# ProDocument_esp32_brewpiless_2024-01-04.net
KiCad netlist of a schematic drawn in EasyEDA Pro
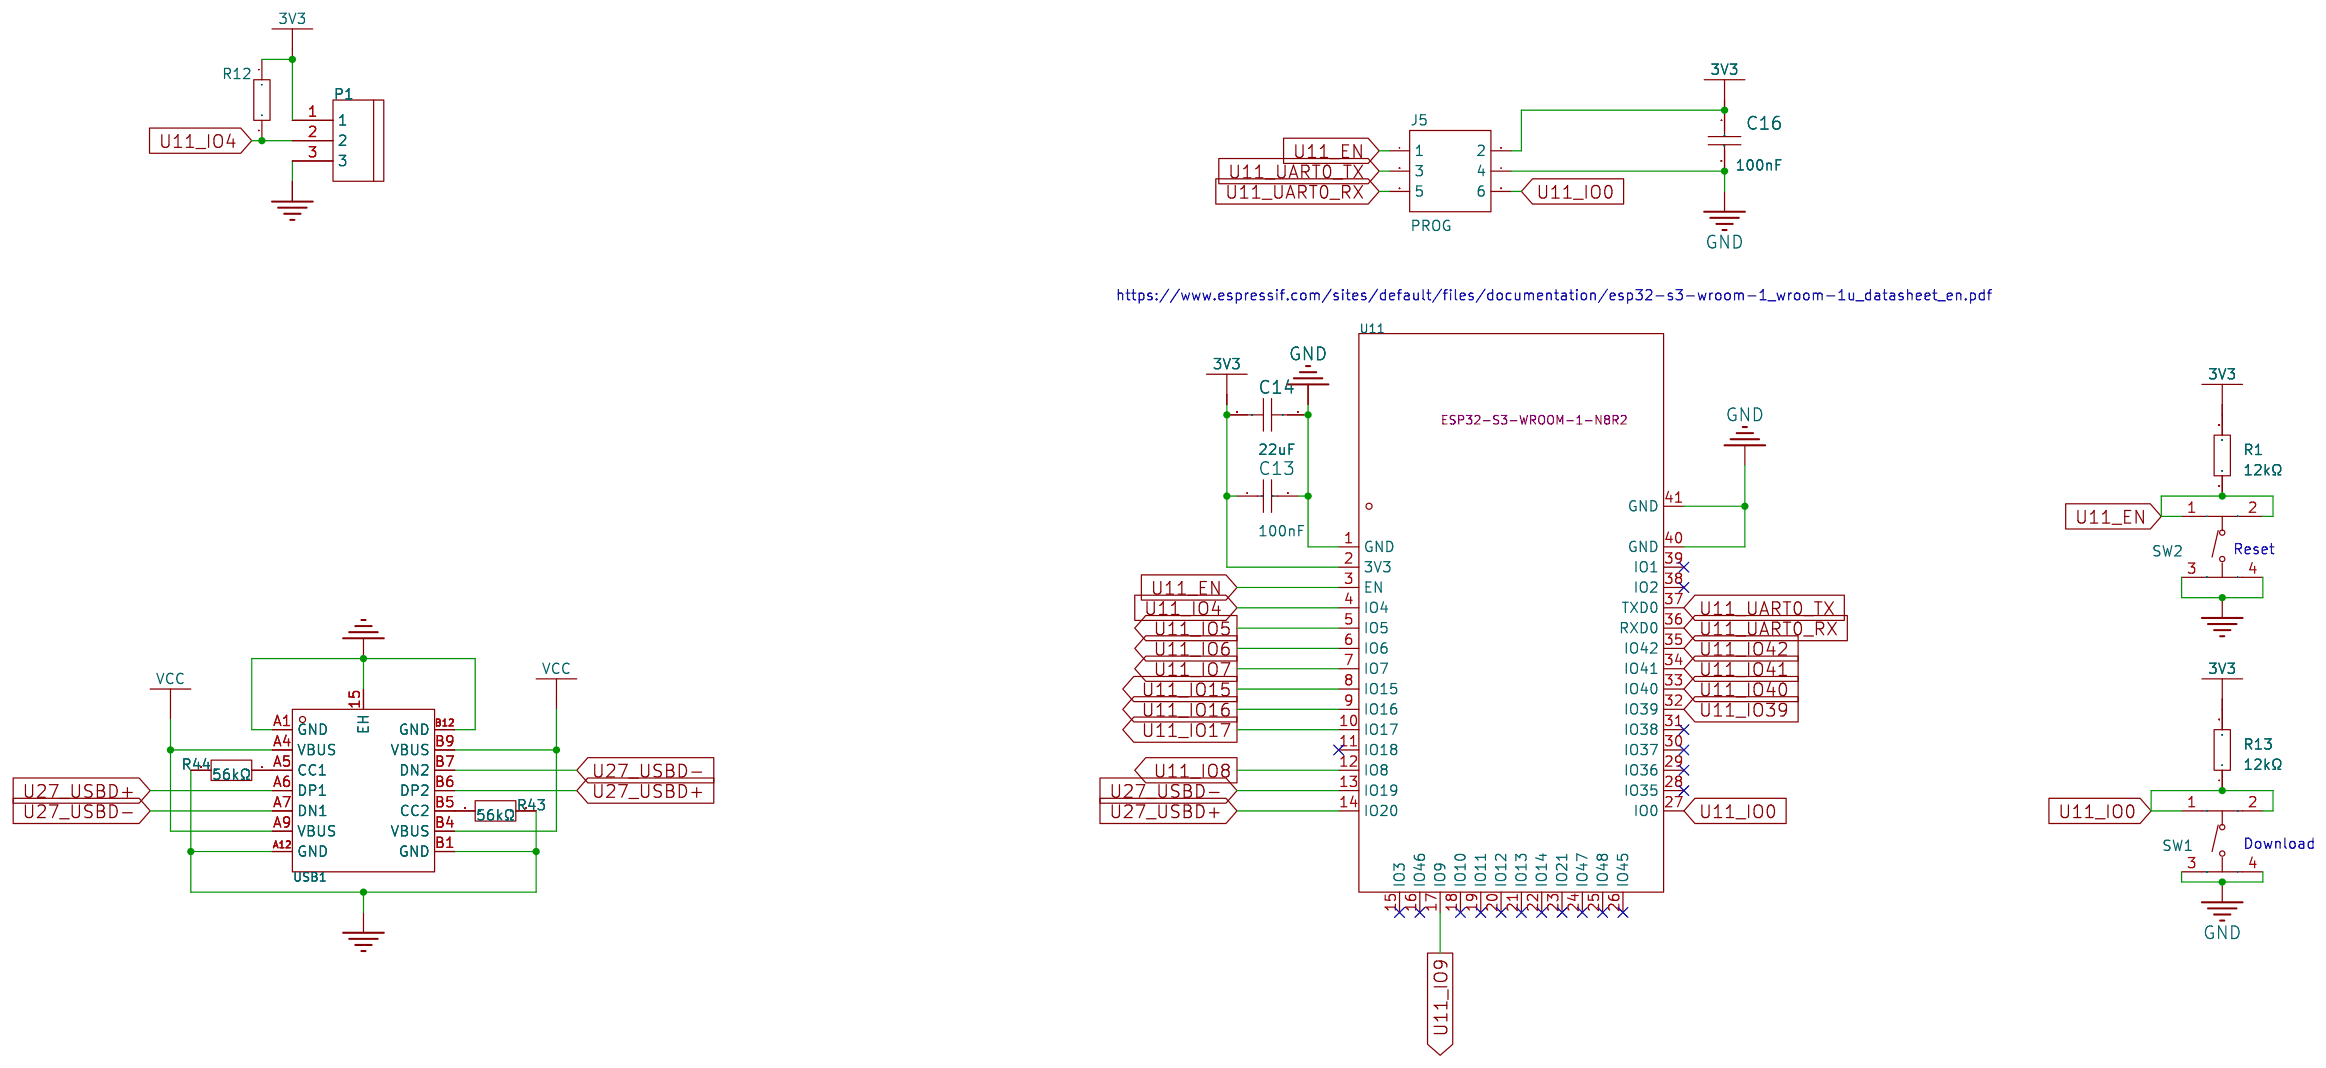
[diagram p0: ESP32]
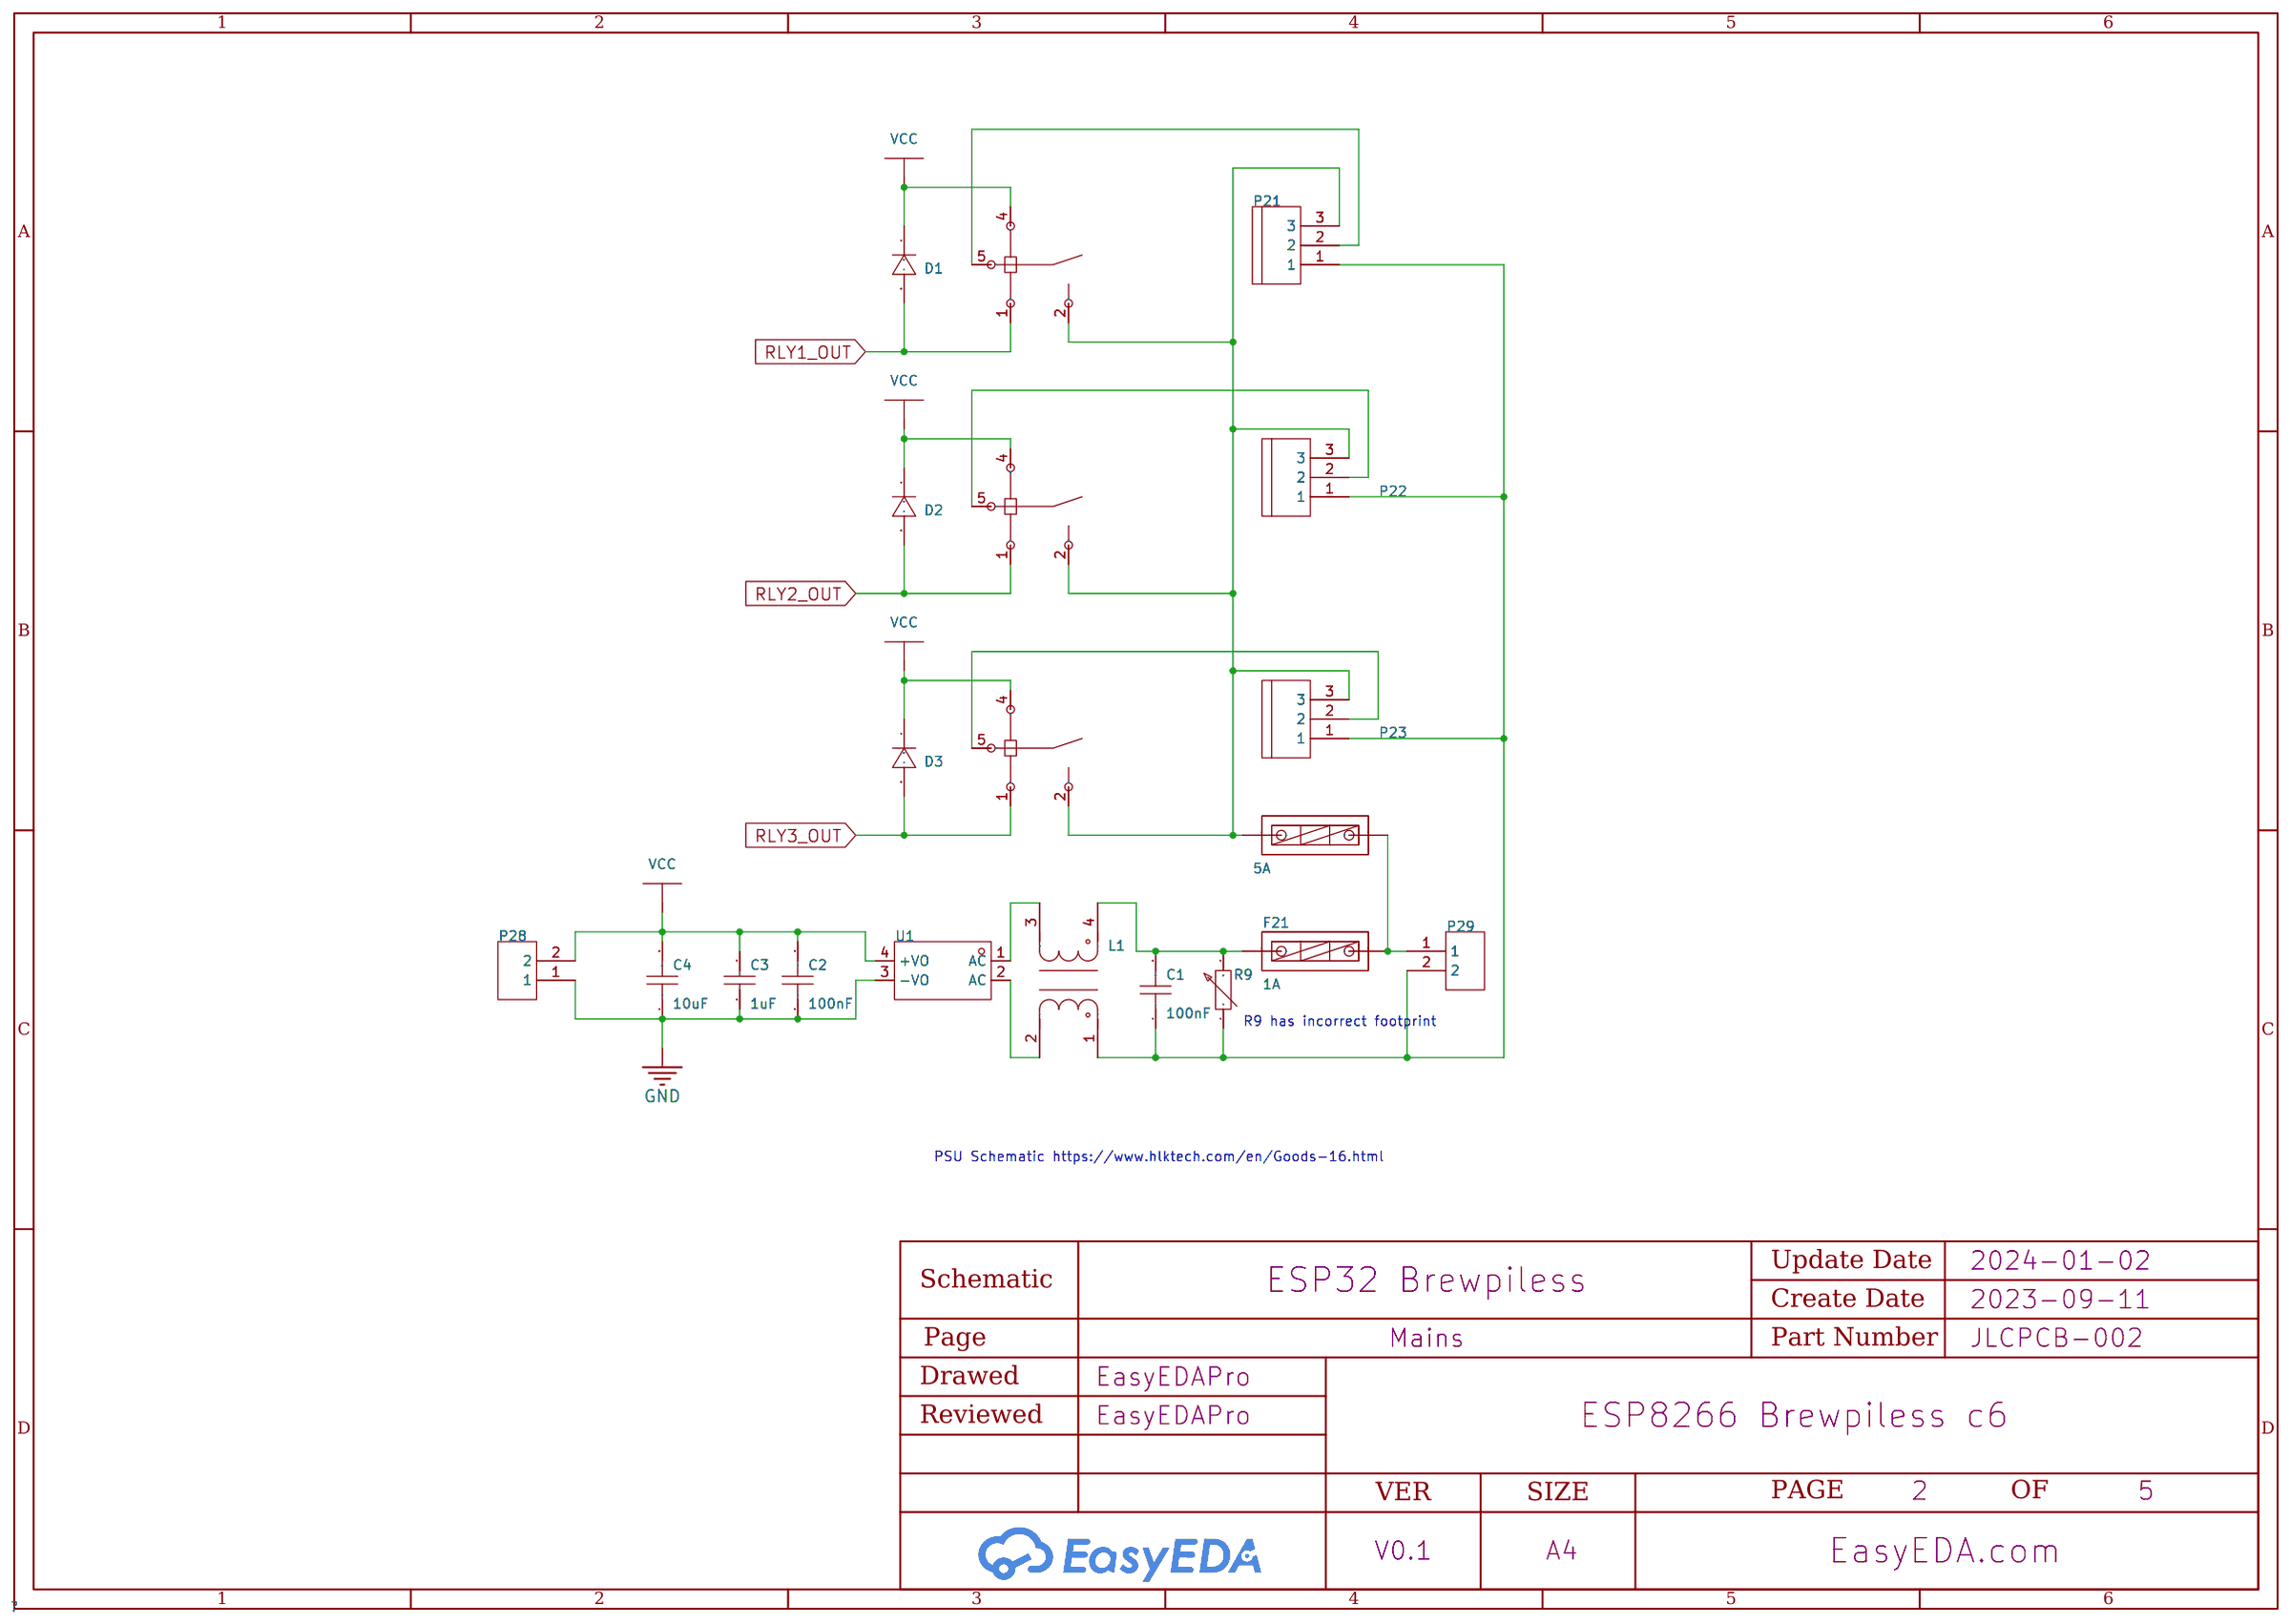
[diagram p1: Mains]
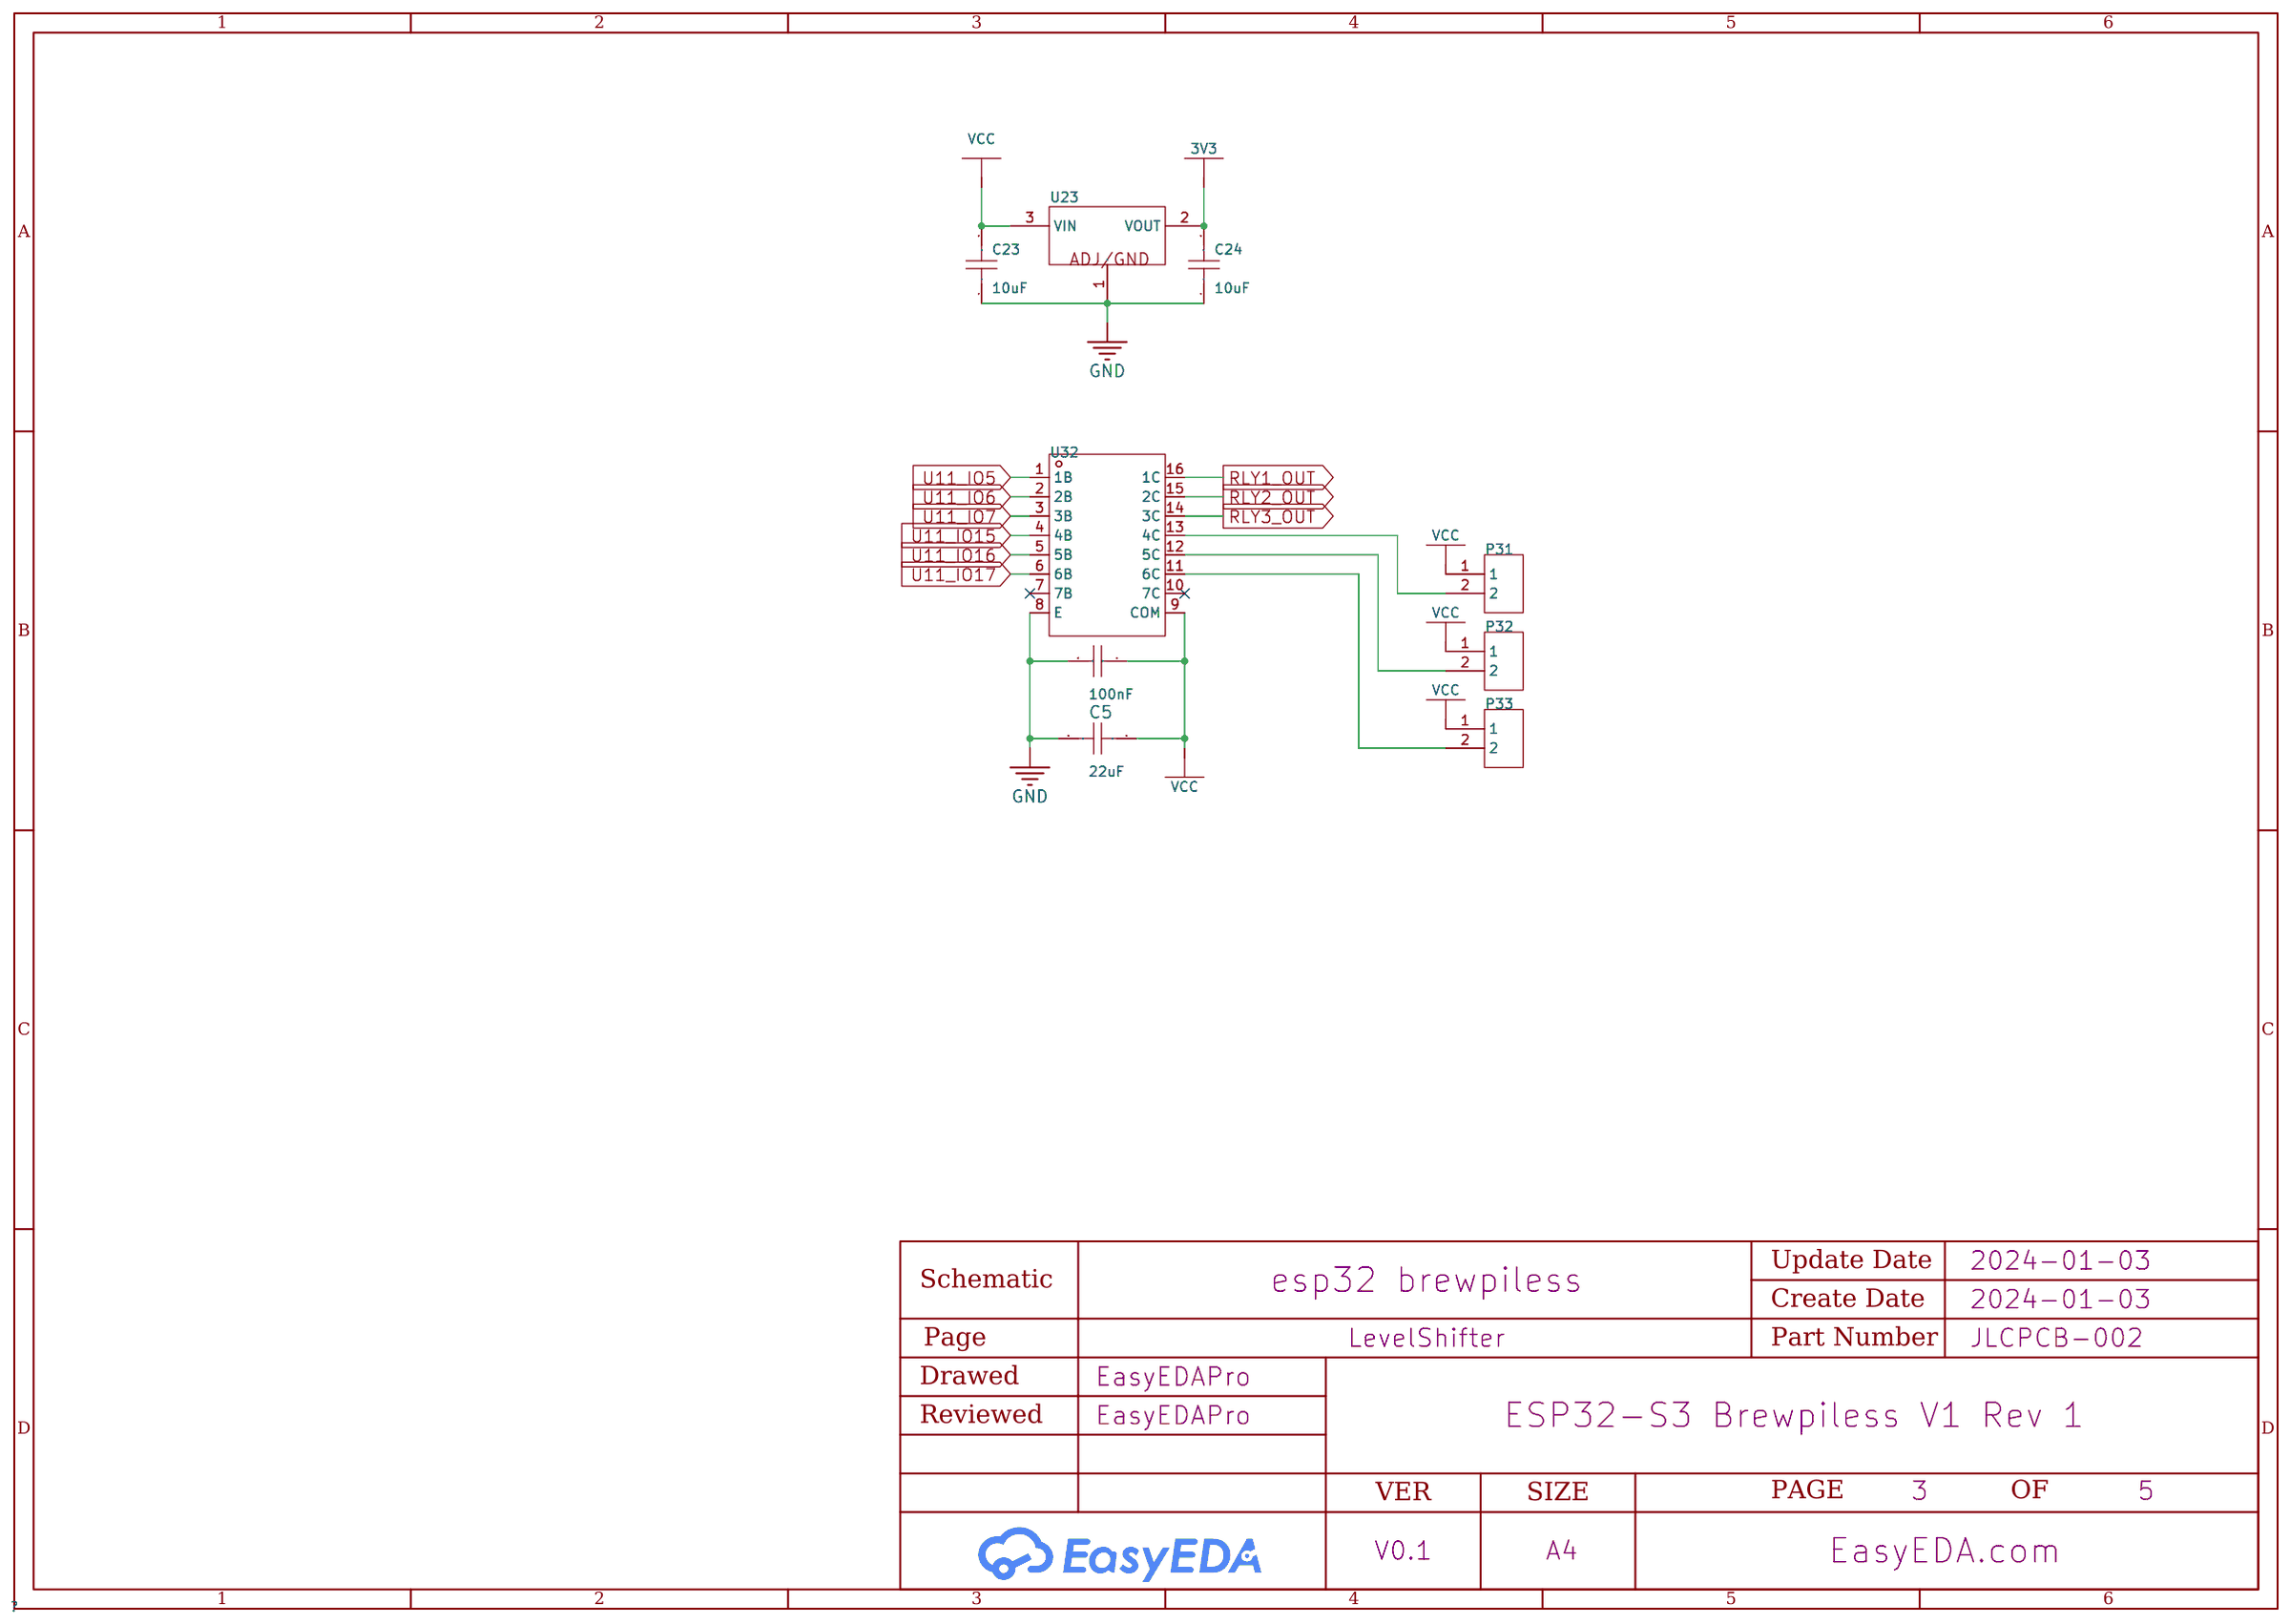
[diagram p2: LevelShifter]
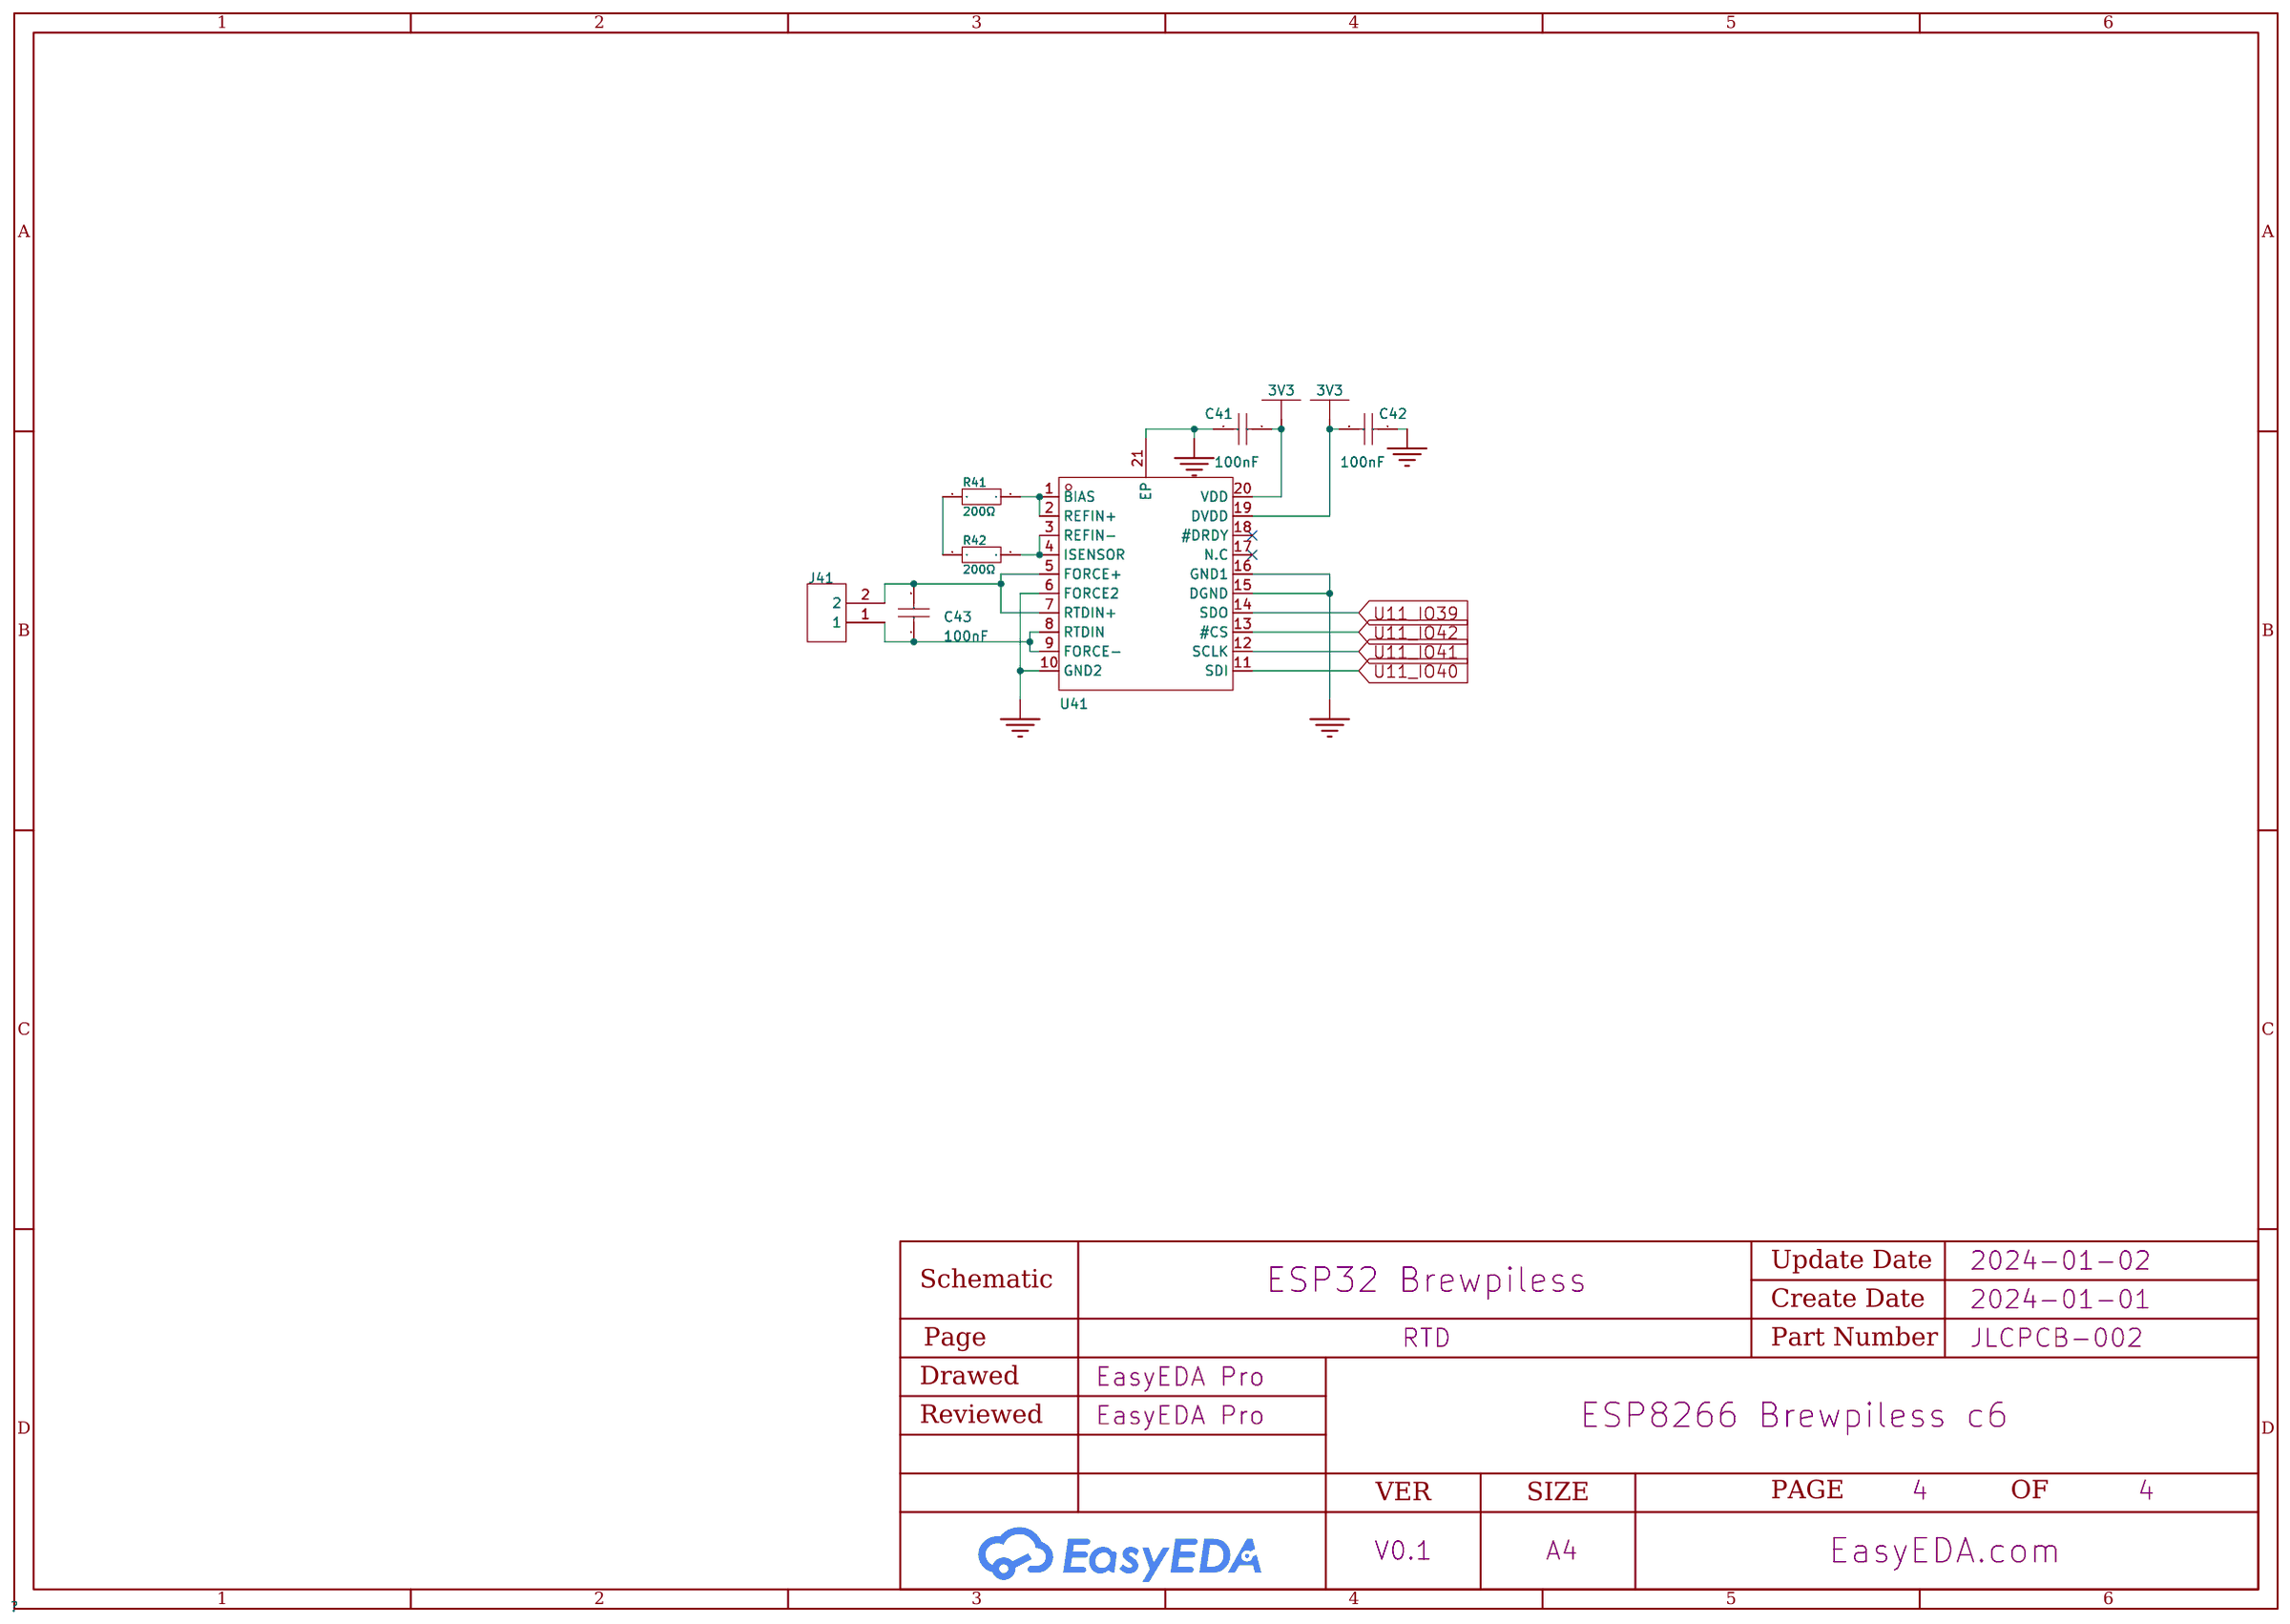
[diagram p3: RTD]
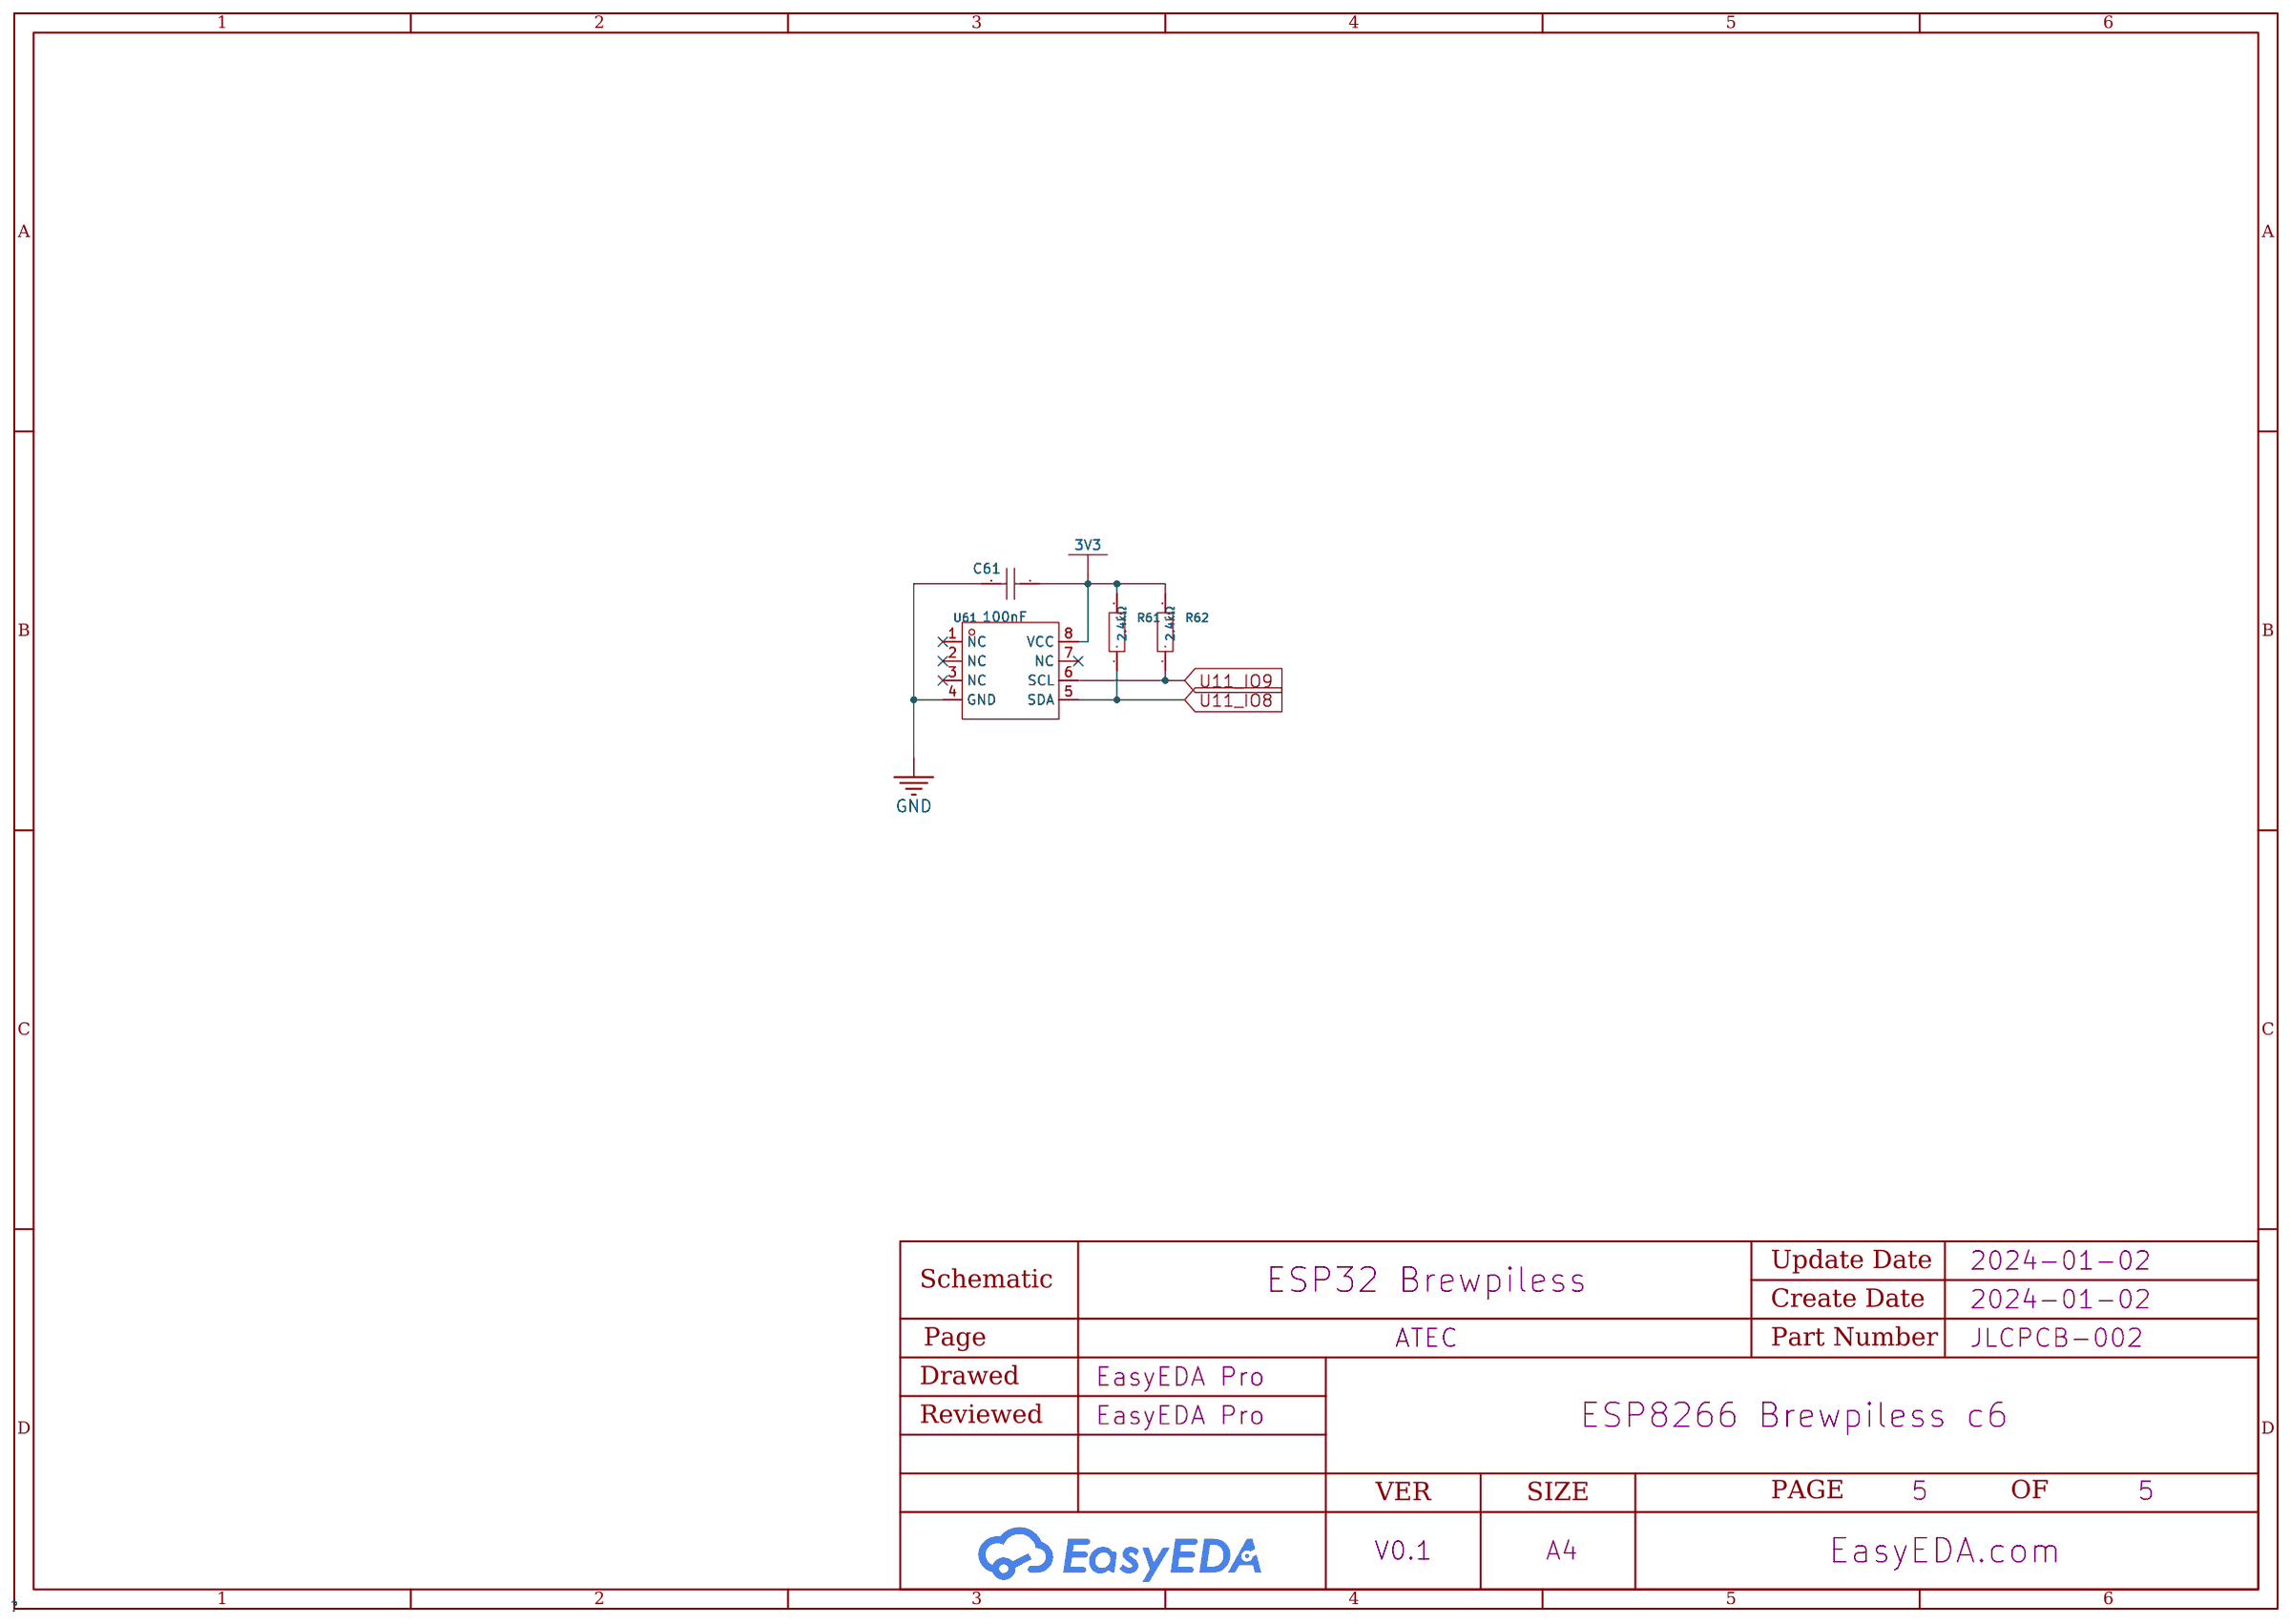
[diagram p4: ATEC]

(export (version "E")
  (design (tool "Eeschema 10.0.6"))
  (components
    (comp (ref "C13")
      (value "100nF")
      (footprint "easyedapro:C0805")
      (fields
        (field (name "Manufacturer Part") "CC0805KRX7R9BB104")
        (field (name "Manufacturer") "YAGEO(国巨)")
      )
      (libsource (lib "easyedapro") (part "CC0805KRX7R9BB104"))
    )
    (comp (ref "C14")
      (value "22uF")
      (footprint "easyedapro:C0805")
      (fields
        (field (name "Manufacturer Part") "CL21A226MAQNNNE")
        (field (name "Manufacturer") "SAMSUNG(三星)")
      )
      (libsource (lib "easyedapro") (part "CL21A226MAQNNNE"))
    )
    (comp (ref "C16")
      (value "100nF")
      (footprint "easyedapro:C0805")
      (fields
        (field (name "Manufacturer Part") "CC0805KRX7R9BB104")
        (field (name "Manufacturer") "YAGEO(国巨)")
      )
      (libsource (lib "easyedapro") (part "CC0805KRX7R9BB104"))
    )
    (comp (ref "J5")
      (value "PROG")
      (footprint "easyedapro:IDC-TH_6P-P2.54_C11214")
      (fields (field (name "Manufacturer Part") "2.54-2*3P简牛") (field (name "Manufacturer") "BOOMELE(博穆精密)"))
      (libsource (lib "easyedapro") (part "HDR-IDC-2.54-2X3P"))
    )
    (comp (ref "P1")
      (value "WJ500V-5.08-3P")
      (footprint "easyedapro:CONN-TH_3P-P5.00_WJ500V-5.08-3P")
      (fields (field (name "Manufacturer") "KANGNEX(康奈克斯电气)"))
      (libsource (lib "easyedapro") (part "WJ500V-5.08-3P-14-00A"))
    )
    (comp (ref "R1")
      (value "12kΩ")
      (footprint "easyedapro:R0805")
      (fields
        (field (name "Manufacturer Part") "0805W8F1202T5E")
        (field (name "Manufacturer") "UNI-ROYAL(厚声)")
      )
      (libsource (lib "easyedapro") (part "0805W8F1202T5E"))
    )
    (comp (ref "R12")
      (value "4.7kΩ")
      (footprint "easyedapro:R0805")
      (fields
        (field (name "Manufacturer Part") "0805W8F4701T5E")
        (field (name "Manufacturer") "UNI-ROYAL(厚声)")
      )
      (libsource (lib "easyedapro") (part "0805W8F4701T5E"))
    )
    (comp (ref "R13")
      (value "12kΩ")
      (footprint "easyedapro:R0805")
      (fields
        (field (name "Manufacturer Part") "0805W8F1202T5E")
        (field (name "Manufacturer") "UNI-ROYAL(厚声)")
      )
      (libsource (lib "easyedapro") (part "0805W8F1202T5E"))
    )
    (comp (ref "R43")
      (value "56kΩ")
      (footprint "easyedapro:R0805")
      (fields (field (name "Manufacturer Part") "ARG05DTC5602") (field (name "Manufacturer") "Viking(光颉)"))
      (libsource (lib "easyedapro") (part "ARG05DTC5602"))
    )
    (comp (ref "R44")
      (value "56kΩ")
      (footprint "easyedapro:R0805")
      (fields (field (name "Manufacturer Part") "ARG05DTC5602") (field (name "Manufacturer") "Viking(光颉)"))
      (libsource (lib "easyedapro") (part "ARG05DTC5602"))
    )
    (comp (ref "SW1")
      (value "TS-1187A-B-A-B")
      (footprint "easyedapro:SW-SMD_4P-L5.1-W5.1-P3.70-LS6.5-TL-2")
      (fields (field (name "Manufacturer") "XKB Connectivity(中国星坤)"))
      (libsource (lib "easyedapro") (part "TS-1187A-B-A-B"))
    )
    (comp (ref "SW2")
      (value "TS-1187A-B-A-B")
      (footprint "easyedapro:SW-SMD_4P-L5.1-W5.1-P3.70-LS6.5-TL-2")
      (fields (field (name "Manufacturer") "XKB Connectivity(中国星坤)"))
      (libsource (lib "easyedapro") (part "TS-1187A-B-A-B"))
    )
    (comp (ref "U11")
      (value "2.4GHz")
      (footprint "easyedapro:WIRELM-SMD_ESP32-S3-WROOM-1")
      (description "Core Processor:ESP32-S3芯片 Support Interface:I2C；GPIO；SPI；PWM；ADC；UART；USB；I2S Frequency:2.4GHz")
      (fields
        (field (name "Manufacturer Part") "ESP32-S3-WROOM-1-N8R2")
        (field (name "Manufacturer") "ESPRESSIF(乐鑫)")
      )
      (libsource (lib "easyedapro") (part "ESP32-S3-WROOM-1(N8R2)"))
    )
    (comp (ref "USB1")
      (value "TYPE-C 14P LTH10.0")
      (footprint "easyedapro:TYPE-C-SMD_918-468K2029Y50001")
      (fields (field (name "Manufacturer") "SHOU HAN(首韩)"))
      (libsource (lib "easyedapro") (part "TYPE-C 14P LTH10.0"))
    )
    (comp (ref "C1")
      (value "100nF")
      (footprint "easyedapro:CAP-TH_L12.0-W5.5-P10.00-D0.6")
      (fields
        (field (name "Manufacturer Part") "MPP104J2W10AJ22620")
        (field (name "Manufacturer") "KNSCHA(科尼盛)")
      )
      (libsource (lib "easyedapro") (part "MPP104J2W10AJ22620"))
    )
    (comp (ref "C2")
      (value "100nF")
      (footprint "easyedapro:CAP-TH_L12.0-W5.5-P10.00-D0.6")
      (fields
        (field (name "Manufacturer Part") "MPP104J2W10AJ22620")
        (field (name "Manufacturer") "KNSCHA(科尼盛)")
      )
      (libsource (lib "easyedapro") (part "MPP104J2W10AJ22620"))
    )
    (comp (ref "C3")
      (value "1uF")
      (footprint "easyedapro:C0805")
      (fields
        (field (name "Manufacturer Part") "CL21B105KBFNNNE")
        (field (name "Manufacturer") "SAMSUNG(三星)")
      )
      (libsource (lib "easyedapro") (part "CL21B105KBFNNNE"))
    )
    (comp (ref "C4")
      (value "10uF")
      (footprint "easyedapro:C0805")
      (fields
        (field (name "Manufacturer Part") "GRM21BR61H106KE43L")
        (field (name "Manufacturer") "muRata(村田)")
      )
      (libsource (lib "easyedapro") (part "GRM21BR61H106KE43L"))
    )
    (comp (ref "D1")
      (value "SM4007PL")
      (footprint "easyedapro:SOD-123F_L2.8-W1.8-LS3.7-RD")
      (fields (field (name "Manufacturer") "MDD"))
      (libsource (lib "easyedapro") (part "SM4007PL"))
    )
    (comp (ref "D2")
      (value "SM4007PL")
      (footprint "easyedapro:SOD-123F_L2.8-W1.8-LS3.7-RD")
      (fields (field (name "Manufacturer") "MDD"))
      (libsource (lib "easyedapro") (part "SM4007PL"))
    )
    (comp (ref "D3")
      (value "SM4007PL")
      (footprint "easyedapro:SOD-123F_L2.8-W1.8-LS3.7-RD")
      (fields (field (name "Manufacturer") "MDD"))
      (libsource (lib "easyedapro") (part "SM4007PL"))
    )
    (comp (ref "F21")
      (value "~")
      (footprint "easyedapro:FUSE-TH_5X20RHOSFUSECLIP-SEAT")
      (fields (field (name "Manufacturer Part") "5x20环保保险管夹/座") (field (name "Manufacturer") "xcfuse(旭程)"))
      (libsource (lib "easyedapro") (part "5x20 RHOS Fuse clip/seat"))
    )
    (comp (ref "F22")
      (value "5A")
      (footprint "easyedapro:FUSE-TH_5X20RHOSFUSECLIP-SEAT")
      (fields (field (name "Manufacturer Part") "5x20环保保险管夹/座") (field (name "Manufacturer") "xcfuse(旭程)"))
      (libsource (lib "easyedapro") (part "5x20 RHOS Fuse clip/seat"))
    )
    (comp (ref "F210")
      (value "1A")
      (footprint "easyedapro:FUSE-TH_5X20RHOSFUSECLIP-SEAT")
      (fields (field (name "Manufacturer Part") "5x20环保保险管夹/座") (field (name "Manufacturer") "xcfuse(旭程)"))
      (libsource (lib "easyedapro") (part "5x20 RHOS Fuse clip/seat"))
    )
    (comp (ref "F220")
      (value "10A")
      (footprint "easyedapro:FUSE-TH_5X20RHOSFUSECLIP-SEAT")
      (fields (field (name "Manufacturer Part") "5x20环保保险管夹/座") (field (name "Manufacturer") "xcfuse(旭程)"))
      (libsource (lib "easyedapro") (part "5x20 RHOS Fuse clip/seat"))
    )
    (comp (ref "K1")
      (value "~")
      (footprint "easyedapro:RELAY-TH_973-XXVDC-SL-A")
      (fields
        (field (name "Manufacturer Part") "973-5VDC-SL-A15A250VAC")
        (field (name "Manufacturer") "NHC(汇龙仓)")
      )
      (libsource (lib "easyedapro") (part "973-5VDC-SL-A 15A250VAC"))
    )
    (comp (ref "K2")
      (value "~")
      (footprint "easyedapro:RELAY-TH_973-XXVDC-SL-A")
      (fields
        (field (name "Manufacturer Part") "973-5VDC-SL-A15A250VAC")
        (field (name "Manufacturer") "NHC(汇龙仓)")
      )
      (libsource (lib "easyedapro") (part "973-5VDC-SL-A 15A250VAC"))
    )
    (comp (ref "K3")
      (value "~")
      (footprint "easyedapro:RELAY-TH_973-XXVDC-SL-A")
      (fields
        (field (name "Manufacturer Part") "973-5VDC-SL-A15A250VAC")
        (field (name "Manufacturer") "NHC(汇龙仓)")
      )
      (libsource (lib "easyedapro") (part "973-5VDC-SL-A 15A250VAC"))
    )
    (comp (ref "L1")
      (value "~")
      (footprint "easyedapro:FILTER-TH_UU10.5Y-10MH")
      (description "Number of Lines:2 Inductance @ Frequency:10mH@1kHz DC Resistance (DCR):750mΩ")
      (fields (field (name "Manufacturer Part") "UU10.5Y-10mH") (field (name "Manufacturer") "FH(风华)"))
      (libsource (lib "easyedapro") (part "UU10.5Y-10mH"))
    )
    (comp (ref "P21")
      (value "WJ500V-5.08-3P")
      (footprint "easyedapro:CONN-TH_3P-P5.00_WJ500V-5.08-3P")
      (fields (field (name "Manufacturer") "KANGNEX(康奈克斯电气)"))
      (libsource (lib "easyedapro") (part "WJ500V-5.08-3P-14-00A"))
    )
    (comp (ref "P22")
      (value "WJ500V-5.08-3P")
      (footprint "easyedapro:CONN-TH_3P-P5.00_WJ500V-5.08-3P")
      (fields (field (name "Manufacturer") "KANGNEX(康奈克斯电气)"))
      (libsource (lib "easyedapro") (part "WJ500V-5.08-3P-14-00A"))
    )
    (comp (ref "P23")
      (value "WJ500V-5.08-3P")
      (footprint "easyedapro:CONN-TH_3P-P5.00_WJ500V-5.08-3P")
      (fields (field (name "Manufacturer") "KANGNEX(康奈克斯电气)"))
      (libsource (lib "easyedapro") (part "WJ500V-5.08-3P-14-00A"))
    )
    (comp (ref "P28")
      (value "WJ500V-5.08-2P")
      (footprint "easyedapro:CONN-TH_2P-P5.00_WJ500V-5.08-2P")
      (fields (field (name "Manufacturer") "KANGNEX(康奈克斯电气)"))
      (libsource (lib "easyedapro") (part "WJ500V-5.08-2P-14-00A"))
    )
    (comp (ref "P29")
      (value "WJ500V-5.08-2P")
      (footprint "easyedapro:CONN-TH_2P-P5.00_WJ500V-5.08-2P")
      (fields (field (name "Manufacturer") "KANGNEX(康奈克斯电气)"))
      (libsource (lib "easyedapro") (part "WJ500V-5.08-2P-14-00A"))
    )
    (comp (ref "R9")
      (value "10D561K")
      (footprint "easyedapro:RES-TH_L13.0-W6.0-P7.50-D0.9-S6.00")
      (fields (field (name "Manufacturer") "HEL(鸿志)"))
      (libsource (lib "easyedapro") (part "10D561K"))
    )
    (comp (ref "U1")
      (value "~")
      (footprint "easyedapro:PWRM-TH_HLK-5M05")
      (fields (field (name "Manufacturer Part") "HLK-5M05") (field (name "Manufacturer") "HI-LINK(海凌科)"))
      (libsource (lib "easyedapro") (part "HLK-5M05"))
    )
    (comp (ref "C5")
      (value "22uF")
      (footprint "easyedapro:C0805")
      (fields
        (field (name "Manufacturer Part") "CL21A226MAQNNNE")
        (field (name "Manufacturer") "SAMSUNG(三星)")
      )
      (libsource (lib "easyedapro") (part "CL21A226MAQNNNE"))
    )
    (comp (ref "C22")
      (value "100nF")
      (footprint "easyedapro:C0805")
      (fields
        (field (name "Manufacturer Part") "CC0805KRX7R9BB104")
        (field (name "Manufacturer") "YAGEO(国巨)")
      )
      (libsource (lib "easyedapro") (part "CC0805KRX7R9BB104"))
    )
    (comp (ref "C23")
      (value "10uF")
      (footprint "easyedapro:C0805")
      (fields
        (field (name "Manufacturer Part") "GRM21BR61H106KE43L")
        (field (name "Manufacturer") "muRata(村田)")
      )
      (libsource (lib "easyedapro") (part "GRM21BR61H106KE43L"))
    )
    (comp (ref "C24")
      (value "10uF")
      (footprint "easyedapro:C0805")
      (fields
        (field (name "Manufacturer Part") "GRM21BR61H106KE43L")
        (field (name "Manufacturer") "muRata(村田)")
      )
      (libsource (lib "easyedapro") (part "GRM21BR61H106KE43L"))
    )
    (comp (ref "P31")
      (value "WJ500V-5.08-2P")
      (footprint "easyedapro:CONN-TH_2P-P5.00_WJ500V-5.08-2P")
      (fields (field (name "Manufacturer") "KANGNEX(康奈克斯电气)"))
      (libsource (lib "easyedapro") (part "WJ500V-5.08-2P-14-00A"))
    )
    (comp (ref "P32")
      (value "WJ500V-5.08-2P")
      (footprint "easyedapro:CONN-TH_2P-P5.00_WJ500V-5.08-2P")
      (fields (field (name "Manufacturer") "KANGNEX(康奈克斯电气)"))
      (libsource (lib "easyedapro") (part "WJ500V-5.08-2P-14-00A"))
    )
    (comp (ref "P33")
      (value "WJ500V-5.08-2P")
      (footprint "easyedapro:CONN-TH_2P-P5.00_WJ500V-5.08-2P")
      (fields (field (name "Manufacturer") "KANGNEX(康奈克斯电气)"))
      (libsource (lib "easyedapro") (part "WJ500V-5.08-2P-14-00A"))
    )
    (comp (ref "U23")
      (value "~")
      (footprint "easyedapro:TO-252-2_L6.6-W6.1-P4.57-LS9.9-TL-CW")
      (fields (field (name "Manufacturer Part") "LM1117RS-3.3") (field (name "Manufacturer") "HTC"))
      (libsource (lib "easyedapro") (part "LM1117RS-3.3"))
    )
    (comp (ref "U32")
      (value "~")
      (footprint "easyedapro:SOIC-16_L9.9-W3.9-P1.27-LS6.0-BL")
      (fields (field (name "Manufacturer Part") "ULN2003ADR") (field (name "Manufacturer") "TI(德州仪器)"))
      (libsource (lib "easyedapro") (part "ULN2003ADR"))
    )
    (comp (ref "C41")
      (value "100nF")
      (footprint "easyedapro:C0805")
      (fields
        (field (name "Manufacturer Part") "CC0805KRX7R9BB104")
        (field (name "Manufacturer") "YAGEO(国巨)")
      )
      (libsource (lib "easyedapro") (part "CC0805KRX7R9BB104"))
    )
    (comp (ref "C42")
      (value "100nF")
      (footprint "easyedapro:C0805")
      (fields
        (field (name "Manufacturer Part") "CC0805KRX7R9BB104")
        (field (name "Manufacturer") "YAGEO(国巨)")
      )
      (libsource (lib "easyedapro") (part "CC0805KRX7R9BB104"))
    )
    (comp (ref "C43")
      (value "100nF")
      (footprint "easyedapro:C0805")
      (fields
        (field (name "Manufacturer Part") "CC0805KRX7R9BB104")
        (field (name "Manufacturer") "YAGEO(国巨)")
      )
      (libsource (lib "easyedapro") (part "CC0805KRX7R9BB104"))
    )
    (comp (ref "J41")
      (value "WJ500V-5.08-2P")
      (footprint "easyedapro:CONN-TH_2P-P5.00_WJ500V-5.08-2P")
      (fields (field (name "Manufacturer") "KANGNEX(康奈克斯电气)"))
      (libsource (lib "easyedapro") (part "WJ500V-5.08-2P-14-00A"))
    )
    (comp (ref "R41")
      (value "200Ω")
      (footprint "easyedapro:R0805")
      (fields
        (field (name "Manufacturer Part") "0805W8F2000T5E")
        (field (name "Manufacturer") "UNI-ROYAL(厚声)")
      )
      (libsource (lib "easyedapro") (part "0805W8F2000T5E"))
    )
    (comp (ref "R42")
      (value "200Ω")
      (footprint "easyedapro:R0805")
      (fields
        (field (name "Manufacturer Part") "0805W8F2000T5E")
        (field (name "Manufacturer") "UNI-ROYAL(厚声)")
      )
      (libsource (lib "easyedapro") (part "0805W8F2000T5E"))
    )
    (comp (ref "U41")
      (value "MAX31865ATP+T")
      (footprint "easyedapro:QFN-20_L5.0-W5.0-P0.65-BL-EP")
      (fields (field (name "Manufacturer") "ADI(亚德诺)"))
      (libsource (lib "easyedapro") (part "MAX31865ATP+T"))
    )
    (comp (ref "C61")
      (value "100nF")
      (footprint "easyedapro:C0805")
      (fields
        (field (name "Manufacturer Part") "CC0805KRX7R9BB104")
        (field (name "Manufacturer") "YAGEO(国巨)")
      )
      (libsource (lib "easyedapro") (part "CC0805KRX7R9BB104"))
    )
    (comp (ref "R61")
      (value "2.4kΩ")
      (footprint "easyedapro:R0805")
      (fields
        (field (name "Manufacturer Part") "0805W8F2401T5E")
        (field (name "Manufacturer") "UNI-ROYAL(厚声)")
      )
      (libsource (lib "easyedapro") (part "0805W8F2401T5E"))
    )
    (comp (ref "R62")
      (value "2.4kΩ")
      (footprint "easyedapro:R0805")
      (fields
        (field (name "Manufacturer Part") "0805W8F2401T5E")
        (field (name "Manufacturer") "UNI-ROYAL(厚声)")
      )
      (libsource (lib "easyedapro") (part "0805W8F2401T5E"))
    )
    (comp (ref "U61")
      (value "ATECC608A-SSHDA-T")
      (footprint "easyedapro:SOIC-8_L4.9-W3.9-P1.27-LS6.0-BL")
      (fields (field (name "Manufacturer") "MICROCHIP(美国微芯)"))
      (libsource (lib "easyedapro") (part "ATECC608A-SSHDA-T_C616024"))
    )
  )
  (nets
    (net (code "1") (name "3V3") (class "Default")
      (node (ref "C13") (pin "1") (pinfunction "1_1") (pintype "input"))
      (node (ref "C14") (pin "2") (pinfunction "2_2") (pintype "input"))
      (node (ref "C16") (pin "1") (pinfunction "1_1") (pintype "input"))
      (node (ref "C24") (pin "2") (pinfunction "2_2") (pintype "input"))
      (node (ref "C41") (pin "2") (pinfunction "2_2") (pintype "input"))
      (node (ref "C42") (pin "2") (pinfunction "2_2") (pintype "input"))
      (node (ref "C61") (pin "2") (pinfunction "2_2") (pintype "input"))
      (node (ref "J5") (pin "2") (pinfunction "2_2") (pintype "input"))
      (node (ref "P1") (pin "1") (pinfunction "1_1") (pintype "input"))
      (node (ref "R1") (pin "2") (pinfunction "2_2") (pintype "input"))
      (node (ref "R12") (pin "1") (pinfunction "1_1") (pintype "input"))
      (node (ref "R13") (pin "2") (pinfunction "2_2") (pintype "input"))
      (node (ref "R61") (pin "2") (pinfunction "2_2") (pintype "input"))
      (node (ref "R62") (pin "2") (pinfunction "2_2") (pintype "input"))
      (node (ref "U11") (pin "2") (pinfunction "3V3_2") (pintype "input"))
      (node (ref "U23") (pin "2") (pinfunction "VOUT_2") (pintype "input"))
      (node (ref "U41") (pin "19") (pinfunction "DVDD_19") (pintype "input"))
      (node (ref "U41") (pin "20") (pinfunction "VDD_20") (pintype "input"))
      (node (ref "U61") (pin "8") (pinfunction "VCC_8") (pintype "input"))
    )
    (net (code "2") (name "GND") (class "Default")
      (node (ref "C13") (pin "2") (pinfunction "2_2") (pintype "input"))
      (node (ref "C14") (pin "1") (pinfunction "1_1") (pintype "input"))
      (node (ref "C16") (pin "2") (pinfunction "2_2") (pintype "input"))
      (node (ref "C2") (pin "1") (pinfunction "1_1") (pintype "input"))
      (node (ref "C22") (pin "2") (pinfunction "2_2") (pintype "input"))
      (node (ref "C23") (pin "1") (pinfunction "1_1") (pintype "input"))
      (node (ref "C24") (pin "1") (pinfunction "1_1") (pintype "input"))
      (node (ref "C3") (pin "1") (pinfunction "1_1") (pintype "input"))
      (node (ref "C4") (pin "1") (pinfunction "1_1") (pintype "input"))
      (node (ref "C41") (pin "1") (pinfunction "1_1") (pintype "input"))
      (node (ref "C42") (pin "1") (pinfunction "1_1") (pintype "input"))
      (node (ref "C5") (pin "2") (pinfunction "2_2") (pintype "input"))
      (node (ref "C61") (pin "1") (pinfunction "1_1") (pintype "input"))
      (node (ref "J5") (pin "4") (pinfunction "4_4") (pintype "input"))
      (node (ref "P1") (pin "3") (pinfunction "3_3") (pintype "input"))
      (node (ref "P28") (pin "1") (pinfunction "1_1") (pintype "input"))
      (node (ref "R43") (pin "1") (pinfunction "1_1") (pintype "input"))
      (node (ref "R44") (pin "2") (pinfunction "2_2") (pintype "input"))
      (node (ref "SW1") (pin "3") (pinfunction "C_3") (pintype "input"))
      (node (ref "SW1") (pin "4") (pinfunction "D_4") (pintype "input"))
      (node (ref "SW2") (pin "3") (pinfunction "C_3") (pintype "input"))
      (node (ref "SW2") (pin "4") (pinfunction "D_4") (pintype "input"))
      (node (ref "U1") (pin "3") (pinfunction "-VO_3") (pintype "input"))
      (node (ref "U11") (pin "1") (pinfunction "GND_1") (pintype "input"))
      (node (ref "U11") (pin "40") (pinfunction "GND_40") (pintype "input"))
      (node (ref "U11") (pin "41") (pinfunction "GND_41") (pintype "input"))
      (node (ref "U23") (pin "1") (pinfunction "ADJ_1") (pintype "input"))
      (node (ref "U32") (pin "8") (pinfunction "E_8") (pintype "input"))
      (node (ref "U41") (pin "10") (pinfunction "GND2_10") (pintype "input"))
      (node (ref "U41") (pin "15") (pinfunction "DGND_15") (pintype "input"))
      (node (ref "U41") (pin "16") (pinfunction "GND1_16") (pintype "input"))
      (node (ref "U41") (pin "21") (pinfunction "EP_21") (pintype "input"))
      (node (ref "U41") (pin "6") (pinfunction "FORCE2_6") (pintype "input"))
      (node (ref "U61") (pin "4") (pinfunction "GND_4") (pintype "input"))
      (node (ref "USB1") (pin "15") (pinfunction "EH_15") (pintype "input"))
      (node (ref "USB1") (pin "A1") (pinfunction "GND_A1") (pintype "input"))
      (node (ref "USB1") (pin "A12") (pinfunction "GND_A12") (pintype "input"))
      (node (ref "USB1") (pin "B1") (pinfunction "GND_B1") (pintype "input"))
      (node (ref "USB1") (pin "B12") (pinfunction "GND_B12") (pintype "input"))
    )
    (net (code "3") (name "Net-(C1-Pad1)") (class "Default")
      (node (ref "C1") (pin "1") (pinfunction "1_1") (pintype "input"))
      (node (ref "L1") (pin "1") (pinfunction "1_1") (pintype "input"))
      (node (ref "P21") (pin "1") (pinfunction "1_1") (pintype "input"))
      (node (ref "P22") (pin "1") (pinfunction "1_1") (pintype "input"))
      (node (ref "P23") (pin "1") (pinfunction "1_1") (pintype "input"))
      (node (ref "P29") (pin "2") (pinfunction "2_2") (pintype "input"))
      (node (ref "R9") (pin "1") (pinfunction "1_1") (pintype "input"))
    )
    (net (code "4") (name "Net-(C1-Pad2)") (class "Default")
      (node (ref "C1") (pin "2") (pinfunction "2_2") (pintype "input"))
      (node (ref "F21") (pin "1") (pinfunction "1_1") (pintype "input"))
      (node (ref "L1") (pin "4") (pinfunction "4_4") (pintype "input"))
      (node (ref "R9") (pin "2") (pinfunction "2_2") (pintype "input"))
    )
    (net (code "5") (name "Net-(F22-Pad1)") (class "Default")
      (node (ref "F22") (pin "1") (pinfunction "1_1") (pintype "input"))
      (node (ref "K1") (pin "2") (pinfunction "2_2") (pintype "input"))
      (node (ref "K2") (pin "2") (pinfunction "2_2") (pintype "input"))
      (node (ref "K3") (pin "2") (pinfunction "2_2") (pintype "input"))
      (node (ref "P21") (pin "3") (pinfunction "3_3") (pintype "input"))
      (node (ref "P22") (pin "3") (pinfunction "3_3") (pintype "input"))
      (node (ref "P23") (pin "3") (pinfunction "3_3") (pintype "input"))
    )
    (net (code "6") (name "Net-(F210-Pad1)") (class "Default")
      (node (ref "F210") (pin "1") (pinfunction "1_1") (pintype "input"))
      (node (ref "F220") (pin "1") (pinfunction "1_1") (pintype "input"))
      (node (ref "P29") (pin "1") (pinfunction "1_1") (pintype "input"))
    )
    (net (code "7") (name "Net-(K1-Pad5)") (class "Default")
      (node (ref "K1") (pin "5") (pinfunction "5_5") (pintype "input"))
      (node (ref "P21") (pin "2") (pinfunction "2_2") (pintype "input"))
    )
    (net (code "8") (name "Net-(K2-Pad5)") (class "Default")
      (node (ref "K2") (pin "5") (pinfunction "5_5") (pintype "input"))
      (node (ref "P22") (pin "2") (pinfunction "2_2") (pintype "input"))
    )
    (net (code "9") (name "Net-(K3-Pad5)") (class "Default")
      (node (ref "K3") (pin "5") (pinfunction "5_5") (pintype "input"))
      (node (ref "P23") (pin "2") (pinfunction "2_2") (pintype "input"))
    )
    (net (code "10") (name "Net-(L1-Pad2)") (class "Default")
      (node (ref "L1") (pin "2") (pinfunction "2_2") (pintype "input"))
      (node (ref "U1") (pin "2") (pinfunction "AC_2") (pintype "input"))
    )
    (net (code "11") (name "Net-(L1-Pad3)") (class "Default")
      (node (ref "L1") (pin "3") (pinfunction "3_3") (pintype "input"))
      (node (ref "U1") (pin "1") (pinfunction "AC_1") (pintype "input"))
    )
    (net (code "12") (name "Net-(R41-Pad2)") (class "Default")
      (node (ref "R41") (pin "2") (pinfunction "2_2") (pintype "input"))
      (node (ref "R42") (pin "2") (pinfunction "2_2") (pintype "input"))
    )
    (net (code "13") (name "Net-(U32-4C)") (class "Default")
      (node (ref "P31") (pin "2") (pinfunction "2_2") (pintype "input"))
      (node (ref "U32") (pin "13") (pinfunction "4C_13") (pintype "input"))
    )
    (net (code "14") (name "Net-(U32-5C)") (class "Default")
      (node (ref "P32") (pin "2") (pinfunction "2_2") (pintype "input"))
      (node (ref "U32") (pin "12") (pinfunction "5C_12") (pintype "input"))
    )
    (net (code "15") (name "Net-(U32-6C)") (class "Default")
      (node (ref "P33") (pin "2") (pinfunction "2_2") (pintype "input"))
      (node (ref "U32") (pin "11") (pinfunction "6C_11") (pintype "input"))
    )
    (net (code "16") (name "Net-(U41-BIAS)") (class "Default")
      (node (ref "R41") (pin "1") (pinfunction "1_1") (pintype "input"))
      (node (ref "U41") (pin "1") (pinfunction "BIAS_1") (pintype "input"))
      (node (ref "U41") (pin "2") (pinfunction "REFIN+_2") (pintype "input"))
    )
    (net (code "17") (name "Net-(U41-FORCE+)") (class "Default")
      (node (ref "C43") (pin "2") (pinfunction "2_2") (pintype "input"))
      (node (ref "J41") (pin "2") (pinfunction "2_2") (pintype "input"))
      (node (ref "U41") (pin "5") (pinfunction "FORCE+_5") (pintype "input"))
      (node (ref "U41") (pin "7") (pinfunction "RTDIN+_7") (pintype "input"))
    )
    (net (code "18") (name "Net-(U41-FORCE-)") (class "Default")
      (node (ref "C43") (pin "1") (pinfunction "1_1") (pintype "input"))
      (node (ref "J41") (pin "1") (pinfunction "1_1") (pintype "input"))
      (node (ref "U41") (pin "8") (pinfunction "RTDIN_8") (pintype "input"))
      (node (ref "U41") (pin "9") (pinfunction "FORCE-_9") (pintype "input"))
    )
    (net (code "19") (name "Net-(U41-ISENSOR)") (class "Default")
      (node (ref "R42") (pin "1") (pinfunction "1_1") (pintype "input"))
      (node (ref "U41") (pin "3") (pinfunction "REFIN-_3") (pintype "input"))
      (node (ref "U41") (pin "4") (pinfunction "ISENSOR_4") (pintype "input"))
    )
    (net (code "20") (name "Net-(USB1-CC1)") (class "Default")
      (node (ref "R44") (pin "1") (pinfunction "1_1") (pintype "input"))
      (node (ref "USB1") (pin "A5") (pinfunction "CC1_A5") (pintype "input"))
    )
    (net (code "21") (name "Net-(USB1-CC2)") (class "Default")
      (node (ref "R43") (pin "2") (pinfunction "2_2") (pintype "input"))
      (node (ref "USB1") (pin "B5") (pinfunction "CC2_B5") (pintype "input"))
    )
    (net (code "22") (name "RLY1_OUT") (class "Default")
      (node (ref "D1") (pin "2") (pinfunction "A_2") (pintype "input"))
      (node (ref "K1") (pin "1") (pinfunction "1_1") (pintype "input"))
      (node (ref "U32") (pin "16") (pinfunction "1C_16") (pintype "input"))
    )
    (net (code "23") (name "RLY2_OUT") (class "Default")
      (node (ref "D2") (pin "2") (pinfunction "A_2") (pintype "input"))
      (node (ref "K2") (pin "1") (pinfunction "1_1") (pintype "input"))
      (node (ref "U32") (pin "15") (pinfunction "2C_15") (pintype "input"))
    )
    (net (code "24") (name "RLY3_OUT") (class "Default")
      (node (ref "D3") (pin "2") (pinfunction "A_2") (pintype "input"))
      (node (ref "K3") (pin "1") (pinfunction "1_1") (pintype "input"))
      (node (ref "U32") (pin "14") (pinfunction "3C_14") (pintype "input"))
    )
    (net (code "25") (name "U11_EN") (class "Default")
      (node (ref "J5") (pin "1") (pinfunction "1_1") (pintype "input"))
      (node (ref "R1") (pin "1") (pinfunction "1_1") (pintype "input"))
      (node (ref "SW2") (pin "1") (pinfunction "A_1") (pintype "input"))
      (node (ref "SW2") (pin "2") (pinfunction "B_2") (pintype "input"))
      (node (ref "U11") (pin "3") (pinfunction "EN_3") (pintype "input"))
    )
    (net (code "26") (name "U11_IO0") (class "Default")
      (node (ref "J5") (pin "6") (pinfunction "6_6") (pintype "input"))
      (node (ref "R13") (pin "1") (pinfunction "1_1") (pintype "input"))
      (node (ref "SW1") (pin "1") (pinfunction "A_1") (pintype "input"))
      (node (ref "SW1") (pin "2") (pinfunction "B_2") (pintype "input"))
      (node (ref "U11") (pin "27") (pinfunction "IO0_27") (pintype "input"))
    )
    (net (code "27") (name "U11_IO4") (class "Default")
      (node (ref "P1") (pin "2") (pinfunction "2_2") (pintype "input"))
      (node (ref "R12") (pin "2") (pinfunction "2_2") (pintype "input"))
      (node (ref "U11") (pin "4") (pinfunction "IO4_4") (pintype "input"))
    )
    (net (code "28") (name "U11_IO5") (class "Default")
      (node (ref "U11") (pin "5") (pinfunction "IO5_5") (pintype "input"))
      (node (ref "U32") (pin "1") (pinfunction "1B_1") (pintype "input"))
    )
    (net (code "29") (name "U11_IO6") (class "Default")
      (node (ref "U11") (pin "6") (pinfunction "IO6_6") (pintype "input"))
      (node (ref "U32") (pin "2") (pinfunction "2B_2") (pintype "input"))
    )
    (net (code "30") (name "U11_IO7") (class "Default")
      (node (ref "U11") (pin "7") (pinfunction "IO7_7") (pintype "input"))
      (node (ref "U32") (pin "3") (pinfunction "3B_3") (pintype "input"))
    )
    (net (code "31") (name "U11_IO8") (class "Default")
      (node (ref "R61") (pin "1") (pinfunction "1_1") (pintype "input"))
      (node (ref "U11") (pin "12") (pinfunction "IO8_12") (pintype "input"))
      (node (ref "U61") (pin "5") (pinfunction "SDA_5") (pintype "input"))
    )
    (net (code "32") (name "U11_IO9") (class "Default")
      (node (ref "R62") (pin "1") (pinfunction "1_1") (pintype "input"))
      (node (ref "U11") (pin "17") (pinfunction "IO9_17") (pintype "input"))
      (node (ref "U61") (pin "6") (pinfunction "SCL_6") (pintype "input"))
    )
    (net (code "33") (name "U11_IO15") (class "Default")
      (node (ref "U11") (pin "8") (pinfunction "IO15_8") (pintype "input"))
      (node (ref "U32") (pin "4") (pinfunction "4B_4") (pintype "input"))
    )
    (net (code "34") (name "U11_IO16") (class "Default")
      (node (ref "U11") (pin "9") (pinfunction "IO16_9") (pintype "input"))
      (node (ref "U32") (pin "5") (pinfunction "5B_5") (pintype "input"))
    )
    (net (code "35") (name "U11_IO17") (class "Default")
      (node (ref "U11") (pin "10") (pinfunction "IO17_10") (pintype "input"))
      (node (ref "U32") (pin "6") (pinfunction "6B_6") (pintype "input"))
    )
    (net (code "36") (name "U11_IO39") (class "Default")
      (node (ref "U11") (pin "32") (pinfunction "IO39_32") (pintype "input"))
      (node (ref "U41") (pin "14") (pinfunction "SDO_14") (pintype "input"))
    )
    (net (code "37") (name "U11_IO40") (class "Default")
      (node (ref "U11") (pin "33") (pinfunction "IO40_33") (pintype "input"))
      (node (ref "U41") (pin "11") (pinfunction "SDI_11") (pintype "input"))
    )
    (net (code "38") (name "U11_IO41") (class "Default")
      (node (ref "U11") (pin "34") (pinfunction "IO41_34") (pintype "input"))
      (node (ref "U41") (pin "12") (pinfunction "SCLK_12") (pintype "input"))
    )
    (net (code "39") (name "U11_IO42") (class "Default")
      (node (ref "U11") (pin "35") (pinfunction "IO42_35") (pintype "input"))
      (node (ref "U41") (pin "13") (pinfunction "#CS_13") (pintype "input"))
    )
    (net (code "40") (name "U11_UART0_RX") (class "Default")
      (node (ref "J5") (pin "5") (pinfunction "5_5") (pintype "input"))
      (node (ref "U11") (pin "36") (pinfunction "RXD0_36") (pintype "input"))
    )
    (net (code "41") (name "U11_UART0_TX") (class "Default")
      (node (ref "J5") (pin "3") (pinfunction "3_3") (pintype "input"))
      (node (ref "U11") (pin "37") (pinfunction "TXD0_37") (pintype "input"))
    )
    (net (code "42") (name "U27_USBD+") (class "Default")
      (node (ref "U11") (pin "14") (pinfunction "IO20_14") (pintype "input"))
      (node (ref "USB1") (pin "A6") (pinfunction "DP1_A6") (pintype "input"))
      (node (ref "USB1") (pin "B6") (pinfunction "DP2_B6") (pintype "input"))
    )
    (net (code "43") (name "U27_USBD-") (class "Default")
      (node (ref "U11") (pin "13") (pinfunction "IO19_13") (pintype "input"))
      (node (ref "USB1") (pin "A7") (pinfunction "DN1_A7") (pintype "input"))
      (node (ref "USB1") (pin "B7") (pinfunction "DN2_B7") (pintype "input"))
    )
    (net (code "44") (name "VCC") (class "Default")
      (node (ref "C2") (pin "2") (pinfunction "2_2") (pintype "input"))
      (node (ref "C22") (pin "1") (pinfunction "1_1") (pintype "input"))
      (node (ref "C23") (pin "2") (pinfunction "2_2") (pintype "input"))
      (node (ref "C3") (pin "2") (pinfunction "2_2") (pintype "input"))
      (node (ref "C4") (pin "2") (pinfunction "2_2") (pintype "input"))
      (node (ref "C5") (pin "1") (pinfunction "1_1") (pintype "input"))
      (node (ref "D1") (pin "1") (pinfunction "C_1") (pintype "input"))
      (node (ref "D2") (pin "1") (pinfunction "C_1") (pintype "input"))
      (node (ref "D3") (pin "1") (pinfunction "C_1") (pintype "input"))
      (node (ref "K1") (pin "4") (pinfunction "4_4") (pintype "input"))
      (node (ref "K2") (pin "4") (pinfunction "4_4") (pintype "input"))
      (node (ref "K3") (pin "4") (pinfunction "4_4") (pintype "input"))
      (node (ref "P28") (pin "2") (pinfunction "2_2") (pintype "input"))
      (node (ref "P31") (pin "1") (pinfunction "1_1") (pintype "input"))
      (node (ref "P32") (pin "1") (pinfunction "1_1") (pintype "input"))
      (node (ref "P33") (pin "1") (pinfunction "1_1") (pintype "input"))
      (node (ref "U1") (pin "4") (pinfunction "+VO_4") (pintype "input"))
      (node (ref "U23") (pin "3") (pinfunction "VIN_3") (pintype "input"))
      (node (ref "U32") (pin "9") (pinfunction "COM_9") (pintype "input"))
      (node (ref "USB1") (pin "A4") (pinfunction "VBUS_A4") (pintype "input"))
      (node (ref "USB1") (pin "A9") (pinfunction "VBUS_A9") (pintype "input"))
      (node (ref "USB1") (pin "B4") (pinfunction "VBUS_B4") (pintype "input"))
      (node (ref "USB1") (pin "B9") (pinfunction "VBUS_B9") (pintype "input"))
    )
    (net (code "45") (name "unconnected-(U11-IO1-Pad39)") (class "Default")
      (node (ref "U11") (pin "39") (pinfunction "IO1_39") (pintype "input+no_connect"))
    )
    (net (code "46") (name "unconnected-(U11-IO2-Pad38)") (class "Default")
      (node (ref "U11") (pin "38") (pinfunction "IO2_38") (pintype "input+no_connect"))
    )
    (net (code "47") (name "unconnected-(U11-IO3-Pad15)") (class "Default")
      (node (ref "U11") (pin "15") (pinfunction "IO3_15") (pintype "input+no_connect"))
    )
    (net (code "48") (name "unconnected-(U11-IO10-Pad18)") (class "Default")
      (node (ref "U11") (pin "18") (pinfunction "IO10_18") (pintype "input+no_connect"))
    )
    (net (code "49") (name "unconnected-(U11-IO11-Pad19)") (class "Default")
      (node (ref "U11") (pin "19") (pinfunction "IO11_19") (pintype "input+no_connect"))
    )
    (net (code "50") (name "unconnected-(U11-IO12-Pad20)") (class "Default")
      (node (ref "U11") (pin "20") (pinfunction "IO12_20") (pintype "input+no_connect"))
    )
    (net (code "51") (name "unconnected-(U11-IO13-Pad21)") (class "Default")
      (node (ref "U11") (pin "21") (pinfunction "IO13_21") (pintype "input+no_connect"))
    )
    (net (code "52") (name "unconnected-(U11-IO14-Pad22)") (class "Default")
      (node (ref "U11") (pin "22") (pinfunction "IO14_22") (pintype "input+no_connect"))
    )
    (net (code "53") (name "unconnected-(U11-IO18-Pad11)") (class "Default")
      (node (ref "U11") (pin "11") (pinfunction "IO18_11") (pintype "input+no_connect"))
    )
    (net (code "54") (name "unconnected-(U11-IO21-Pad23)") (class "Default")
      (node (ref "U11") (pin "23") (pinfunction "IO21_23") (pintype "input+no_connect"))
    )
    (net (code "55") (name "unconnected-(U11-IO35-Pad28)") (class "Default")
      (node (ref "U11") (pin "28") (pinfunction "IO35_28") (pintype "input+no_connect"))
    )
    (net (code "56") (name "unconnected-(U11-IO36-Pad29)") (class "Default")
      (node (ref "U11") (pin "29") (pinfunction "IO36_29") (pintype "input+no_connect"))
    )
    (net (code "57") (name "unconnected-(U11-IO37-Pad30)") (class "Default")
      (node (ref "U11") (pin "30") (pinfunction "IO37_30") (pintype "input+no_connect"))
    )
    (net (code "58") (name "unconnected-(U11-IO38-Pad31)") (class "Default")
      (node (ref "U11") (pin "31") (pinfunction "IO38_31") (pintype "input+no_connect"))
    )
    (net (code "59") (name "unconnected-(U11-IO45-Pad26)") (class "Default")
      (node (ref "U11") (pin "26") (pinfunction "IO45_26") (pintype "input+no_connect"))
    )
    (net (code "60") (name "unconnected-(U11-IO46-Pad16)") (class "Default")
      (node (ref "U11") (pin "16") (pinfunction "IO46_16") (pintype "input+no_connect"))
    )
    (net (code "61") (name "unconnected-(U11-IO47-Pad24)") (class "Default")
      (node (ref "U11") (pin "24") (pinfunction "IO47_24") (pintype "input+no_connect"))
    )
    (net (code "62") (name "unconnected-(U11-IO48-Pad25)") (class "Default")
      (node (ref "U11") (pin "25") (pinfunction "IO48_25") (pintype "input+no_connect"))
    )
    (net (code "63") (name "unconnected-(U32-7B-Pad7)") (class "Default")
      (node (ref "U32") (pin "7") (pinfunction "7B_7") (pintype "input+no_connect"))
    )
    (net (code "64") (name "unconnected-(U32-7C-Pad10)") (class "Default")
      (node (ref "U32") (pin "10") (pinfunction "7C_10") (pintype "input+no_connect"))
    )
    (net (code "65") (name "unconnected-(U41-#DRDY-Pad18)") (class "Default")
      (node (ref "U41") (pin "18") (pinfunction "#DRDY_18") (pintype "input+no_connect"))
    )
    (net (code "66") (name "unconnected-(U41-N.C-Pad17)") (class "Default")
      (node (ref "U41") (pin "17") (pinfunction "N.C_17") (pintype "input+no_connect"))
    )
    (net (code "67") (name "unconnected-(U61-NC-Pad1)") (class "Default")
      (node (ref "U61") (pin "1") (pinfunction "NC_1") (pintype "input+no_connect"))
    )
    (net (code "68") (name "unconnected-(U61-NC-Pad2)") (class "Default")
      (node (ref "U61") (pin "2") (pinfunction "NC_2") (pintype "input+no_connect"))
    )
    (net (code "69") (name "unconnected-(U61-NC-Pad3)") (class "Default")
      (node (ref "U61") (pin "3") (pinfunction "NC_3") (pintype "input+no_connect"))
    )
    (net (code "70") (name "unconnected-(U61-NC-Pad7)") (class "Default")
      (node (ref "U61") (pin "7") (pinfunction "NC_7") (pintype "input+no_connect"))
    )
  )
)
